# power_schematic.net
KiCad netlist of a schematic drawn in Altium Designer
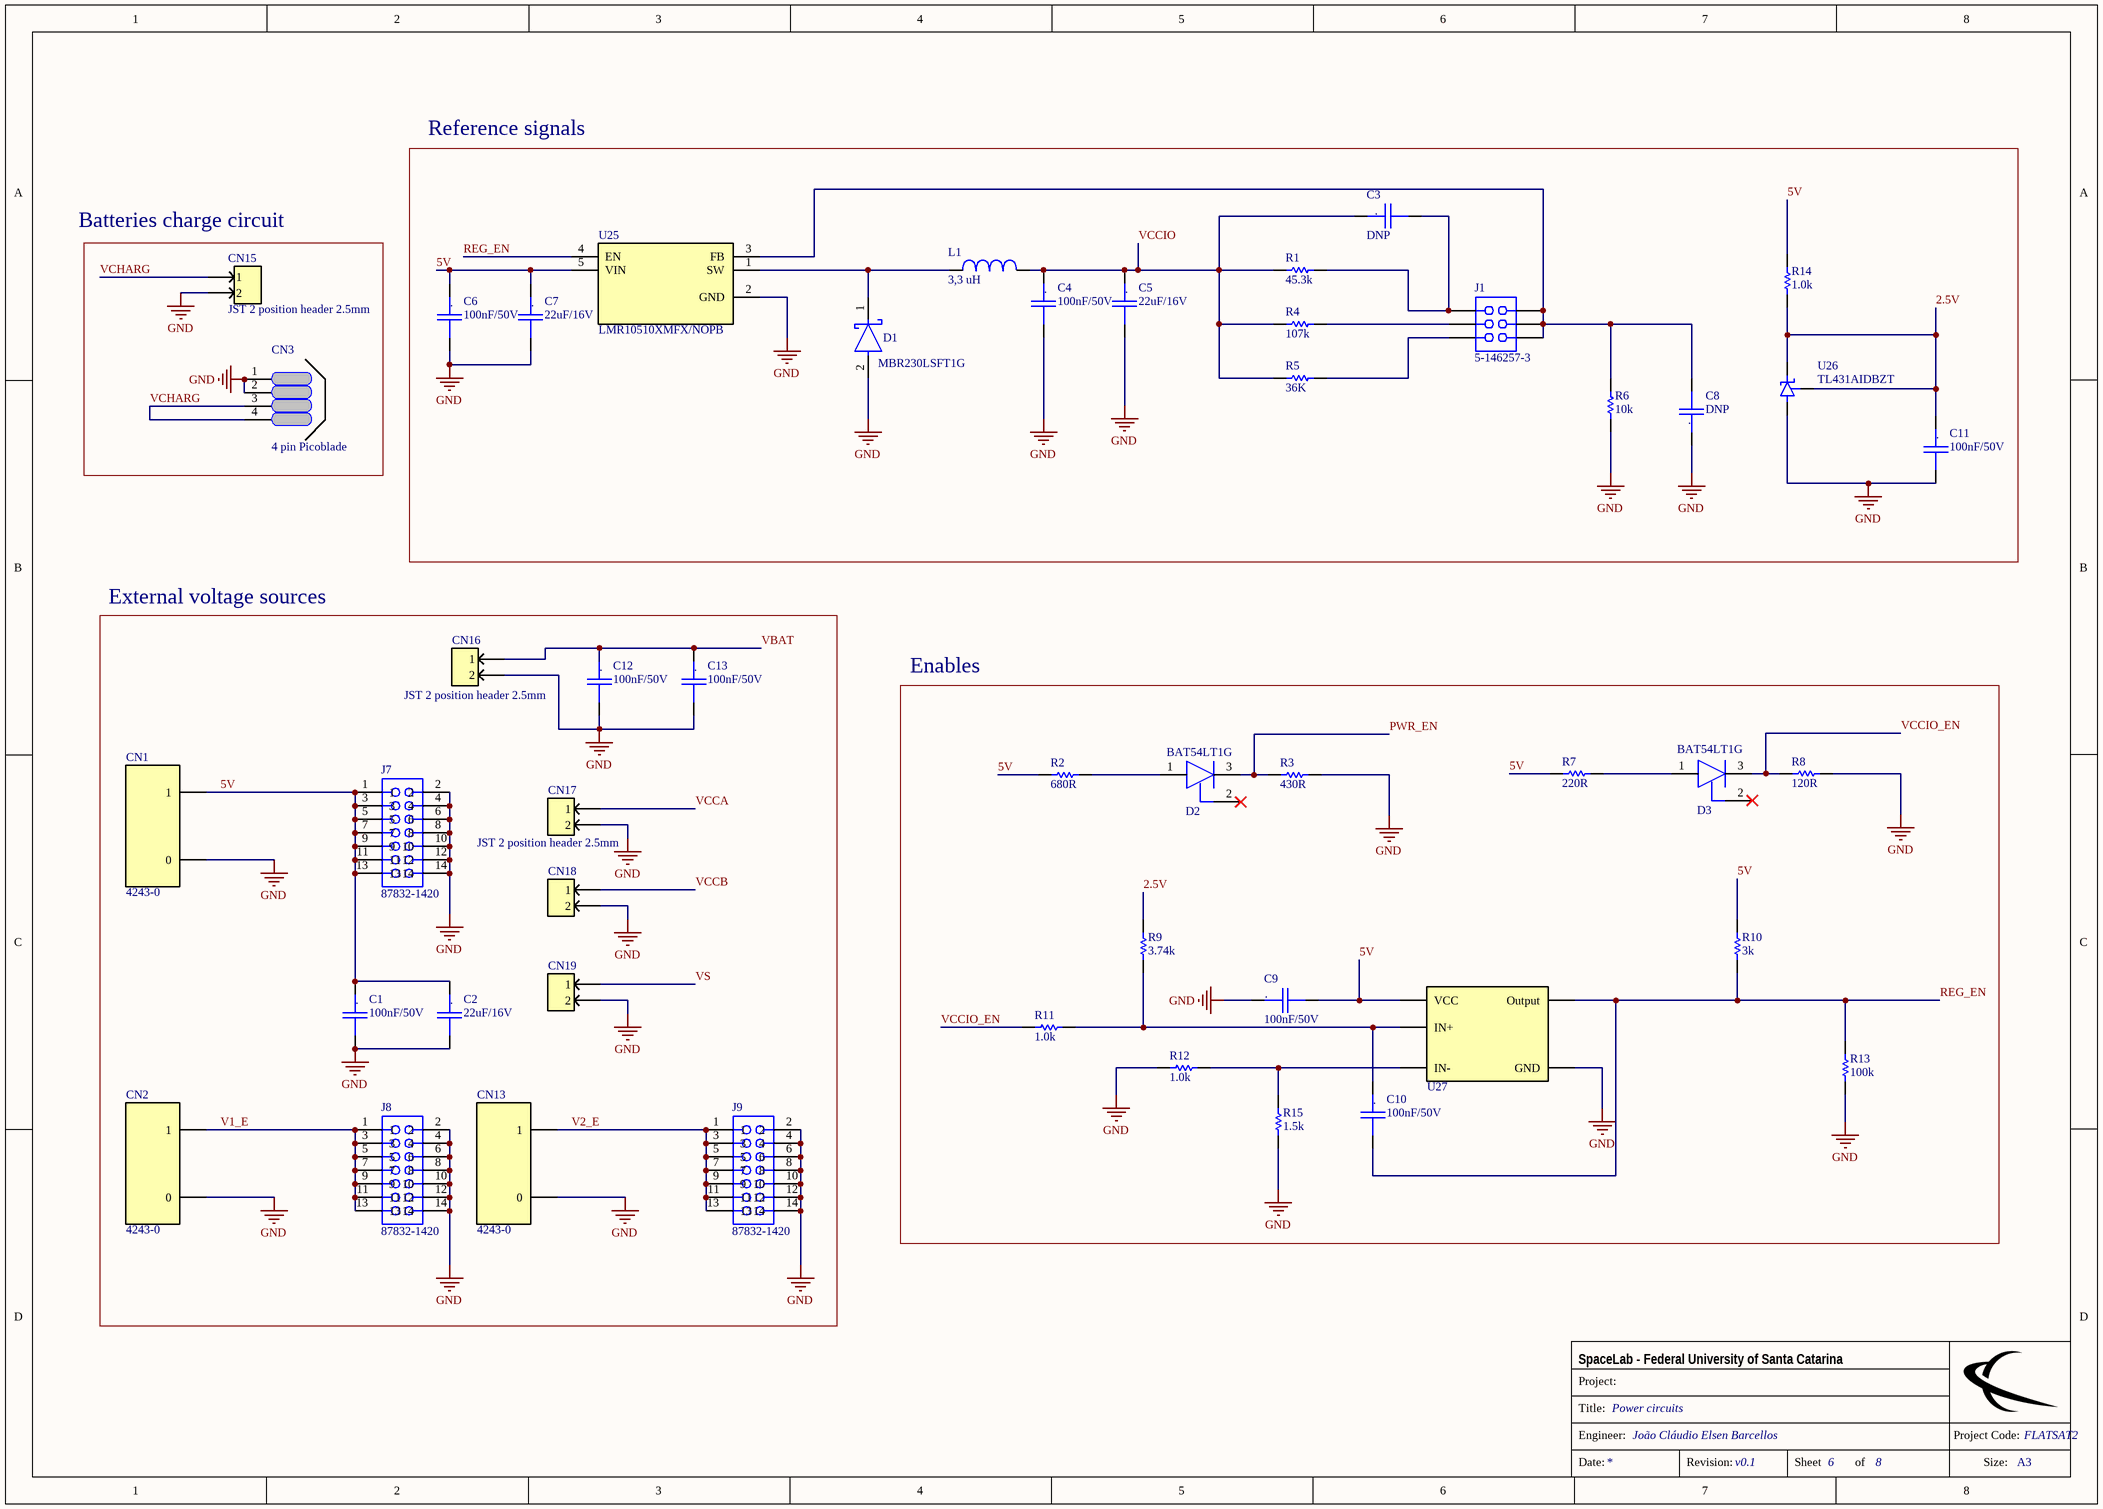
[diagram p0: power_schematic.SchDoc]

(export (version "E")
  (design (tool "Eeschema 10.0.6"))
  (components
    (comp (ref "C1")
      (value "100nF/50V")
      (footprint "CC0603")
      (description "CAP CER 100nF 50V 10% X7R 0603")
      (fields (field (name "MANUFACTURER PART NUMBER") "C0603C104K5RAC3121"))
      (libsource (lib "flatsat_platform_2") (part "Cap_Cer_X7R_100nF_50V_0603"))
    )
    (comp (ref "C2")
      (value "22uF/16V")
      (footprint "CC1210")
      (description "CAP CER 22uF 16V 10% X7R 1210")
      (fields (field (name "MANUFACTURER PART NUMBER") "C3225X7R1C226K250AC"))
      (libsource (lib "flatsat_platform_2") (part "Cap_Cer_X7R_22uF_16V_1210"))
    )
    (comp (ref "C3")
      (value "DNP")
      (footprint "CC0805")
      (description "CAP DNP 0805")
      (libsource (lib "flatsat_platform_2") (part "Cap_DNP_0805"))
    )
    (comp (ref "C4")
      (value "100nF/50V")
      (footprint "CC0603")
      (description "CAP CER 100nF 50V 10% X7R 0603")
      (fields (field (name "MANUFACTURER PART NUMBER") "C0603C104K5RAC3121"))
      (libsource (lib "flatsat_platform_2") (part "Cap_Cer_X7R_100nF_50V_0603"))
    )
    (comp (ref "C5")
      (value "22uF/16V")
      (footprint "CC1210")
      (description "CAP CER 22uF 16V 10% X7R 1210")
      (fields (field (name "MANUFACTURER PART NUMBER") "C3225X7R1C226K250AC"))
      (libsource (lib "flatsat_platform_2") (part "Cap_Cer_X7R_22uF_16V_1210"))
    )
    (comp (ref "C6")
      (value "100nF/50V")
      (footprint "CC0603")
      (description "CAP CER 100nF 50V 10% X7R 0603")
      (fields (field (name "MANUFACTURER PART NUMBER") "C0603C104K5RAC3121"))
      (libsource (lib "flatsat_platform_2") (part "Cap_Cer_X7R_100nF_50V_0603"))
    )
    (comp (ref "C7")
      (value "22uF/16V")
      (footprint "CC1210")
      (description "CAP CER 22uF 16V 10% X7R 1210")
      (fields (field (name "MANUFACTURER PART NUMBER") "C3225X7R1C226K250AC"))
      (libsource (lib "flatsat_platform_2") (part "Cap_Cer_X7R_22uF_16V_1210"))
    )
    (comp (ref "C8")
      (value "DNP")
      (footprint "CC0805")
      (description "CAP DNP 0805")
      (libsource (lib "flatsat_platform_2") (part "Cap_DNP_0805"))
    )
    (comp (ref "C9")
      (value "100nF/50V")
      (footprint "CC0603")
      (description "CAP CER 100nF 50V 10% X7R 0603")
      (fields (field (name "MANUFACTURER PART NUMBER") "C0603C104K5RAC3121"))
      (libsource (lib "flatsat_platform_2") (part "Cap_Cer_X7R_100nF_50V_0603"))
    )
    (comp (ref "C10")
      (value "100nF/50V")
      (footprint "CC0603")
      (description "CAP CER 100nF 50V 10% X7R 0603")
      (fields (field (name "MANUFACTURER PART NUMBER") "C0603C104K5RAC3121"))
      (libsource (lib "flatsat_platform_2") (part "Cap_Cer_X7R_100nF_50V_0603"))
    )
    (comp (ref "C11")
      (value "100nF/50V")
      (footprint "CC0603")
      (description "CAP CER 100nF 50V 10% X7R 0603")
      (fields (field (name "MANUFACTURER PART NUMBER") "C0603C104K5RAC3121"))
      (libsource (lib "flatsat_platform_2") (part "Cap_Cer_X7R_100nF_50V_0603"))
    )
    (comp (ref "C12")
      (value "100nF/50V")
      (footprint "CC0603")
      (description "CAP CER 100nF 50V 10% X7R 0603")
      (fields (field (name "MANUFACTURER PART NUMBER") "C0603C104K5RAC3121"))
      (libsource (lib "flatsat_platform_2") (part "Cap_Cer_X7R_100nF_50V_0603"))
    )
    (comp (ref "C13")
      (value "100nF/50V")
      (footprint "CC0603")
      (description "CAP CER 100nF 50V 10% X7R 0603")
      (fields (field (name "MANUFACTURER PART NUMBER") "C0603C104K5RAC3121"))
      (libsource (lib "flatsat_platform_2") (part "Cap_Cer_X7R_100nF_50V_0603"))
    )
    (comp (ref "CN1")
      (value "4243-0")
      (footprint "4243-0")
      (description "POMONA, 4243-0, Binding Post, 4243 Series, 15 A, 60 VDC, Tin Plated Contacts, Brass, Black")
      (fields (field (name "MANUFACTURER") "Pomona Electronics"))
      (libsource (lib "flatsat_platform_2") (part "4243-0"))
    )
    (comp (ref "CN2")
      (value "4243-0")
      (footprint "4243-0")
      (description "POMONA, 4243-0, Binding Post, 4243 Series, 15 A, 60 VDC, Tin Plated Contacts, Brass, Black")
      (fields (field (name "MANUFACTURER") "Pomona Electronics"))
      (libsource (lib "flatsat_platform_2") (part "4243-0"))
    )
    (comp (ref "CN3")
      (value "4 pin Picoblade")
      (footprint "PICO BLADE 0533980471")
      (description "1.25mm Pitch PicoBlade™ Header, Surface Mount, Vertical, 4 Circuits")
      (fields (field (name "MANUFACTURER") "Molex") (field (name "MANUFACTURER PART NUMBER") "53398-0471"))
      (libsource (lib "flatsat_platform_2") (part "0533980471"))
    )
    (comp (ref "CN13")
      (value "4243-0")
      (footprint "4243-0")
      (description "POMONA, 4243-0, Binding Post, 4243 Series, 15 A, 60 VDC, Tin Plated Contacts, Brass, Black")
      (fields (field (name "MANUFACTURER") "Pomona Electronics"))
      (libsource (lib "flatsat_platform_2") (part "4243-0"))
    )
    (comp (ref "CN15")
      (value "JST 2 position header 2.5mm")
      (footprint "B2B-XH-A-M(LF)(SN)")
      (description "CONN HEADER TOP 2POS 2.5MM GRN")
      (fields
        (field (name "MANUFACTURER") "JST")
        (field (name "MANUFACTURER PART NUMBER") "B2B-XH-A-M(LF)(SN)")
      )
      (libsource (lib "") (part "B2B-XH-A-M(LF)(SN)_1"))
    )
    (comp (ref "CN16")
      (value "JST 2 position header 2.5mm")
      (footprint "B2B-XH-A-M(LF)(SN)")
      (description "CONN HEADER TOP 2POS 2.5MM GRN")
      (fields
        (field (name "MANUFACTURER") "JST")
        (field (name "MANUFACTURER PART NUMBER") "B2B-XH-A-M(LF)(SN)")
      )
      (libsource (lib "flatsat_platform_2") (part "B2B-XH-A-M(LF)(SN)"))
    )
    (comp (ref "CN17")
      (value "JST 2 position header 2.5mm")
      (footprint "B2B-XH-A-M(LF)(SN)")
      (description "CONN HEADER TOP 2POS 2.5MM GRN")
      (fields
        (field (name "MANUFACTURER") "JST")
        (field (name "MANUFACTURER PART NUMBER") "B2B-XH-A-M(LF)(SN)")
      )
      (libsource (lib "flatsat_platform_2") (part "B2B-XH-A-M(LF)(SN)"))
    )
    (comp (ref "CN18")
      (value "JST 2 position header 2.5mm")
      (footprint "B2B-XH-A-M(LF)(SN)")
      (description "CONN HEADER TOP 2POS 2.5MM GRN")
      (fields
        (field (name "MANUFACTURER") "JST")
        (field (name "MANUFACTURER PART NUMBER") "B2B-XH-A-M(LF)(SN)")
      )
      (libsource (lib "flatsat_platform_2") (part "B2B-XH-A-M(LF)(SN)"))
    )
    (comp (ref "CN19")
      (value "JST 2 position header 2.5mm")
      (footprint "B2B-XH-A-M(LF)(SN)")
      (description "CONN HEADER TOP 2POS 2.5MM GRN")
      (fields
        (field (name "MANUFACTURER") "JST")
        (field (name "MANUFACTURER PART NUMBER") "B2B-XH-A-M(LF)(SN)")
      )
      (libsource (lib "flatsat_platform_2") (part "B2B-XH-A-M(LF)(SN)"))
    )
    (comp (ref "D1")
      (value "MBR230LSFT1G")
      (footprint "On_Semiconductor_498_MFG")
      (libsource (lib "flatsat_platform_2") (part "MBR230LSFT1G"))
    )
    (comp (ref "D2")
      (value "BAT54LT1G")
      (footprint "SOT95P237X112-3N")
      (libsource (lib "flatsat_platform_2") (part "BAT54LT1G"))
    )
    (comp (ref "D3")
      (value "BAT54LT1G")
      (footprint "SOT95P237X112-3N")
      (libsource (lib "flatsat_platform_2") (part "BAT54LT1G"))
    )
    (comp (ref "J1")
      (value "5-146257-3")
      (footprint "TE_5-146257-3")
      (description "Header; Breakaway; 0.100 x 0.100 in.; PC Board; Dual; 6; 0.025 in.; 0.12 in.")
      (fields (field (name "MF") "TE Connectivity"))
      (libsource (lib "flatsat_platform_2") (part "5-146257-3"))
    )
    (comp (ref "J7")
      (value "87832-1420")
      (footprint "SAMTEC_TSW-107-05-F-D")
      (description "Connector Header Surface Mount 14 position 0.079 _2.00mm_")
      (fields (field (name "MF") "Molex") (field (name "MANUFACTURER PART NUMBER") "TSW-107-05-F-D"))
      (libsource (lib "flatsat_platform_2") (part "87832-1420"))
    )
    (comp (ref "J8")
      (value "87832-1420")
      (footprint "SAMTEC_TSW-107-05-F-D")
      (description "Connector Header Surface Mount 14 position 0.079 _2.00mm_")
      (fields (field (name "MF") "Molex") (field (name "MANUFACTURER PART NUMBER") "TSW-107-05-F-D"))
      (libsource (lib "flatsat_platform_2") (part "87832-1420"))
    )
    (comp (ref "J9")
      (value "87832-1420")
      (footprint "SAMTEC_TSW-107-05-F-D")
      (description "Connector Header Surface Mount 14 position 0.079 _2.00mm_")
      (fields (field (name "MF") "Molex") (field (name "MANUFACTURER PART NUMBER") "TSW-107-05-F-D"))
      (libsource (lib "flatsat_platform_2") (part "87832-1420"))
    )
    (comp (ref "L1")
      (value "3,3 uH")
      (footprint "SRR6038")
      (description "3.3ÂµH Shielded Wirewound Inductor 3.5A 20mOhm Max Nonstandard")
      (fields (field (name "MF") "Bourns") (field (name "MANUFACTURER PART NUMBER") "SRR6038-3R3Y"))
      (libsource (lib "flatsat_platform_2") (part "3,3 uH"))
    )
    (comp (ref "R1")
      (value "45.3k")
      (footprint "0805")
      (description "RES 45.3K OHM 1/8W 1% 0805")
      (fields (field (name "MANUFACTURER PART NUMBER") "RC0805FR-0745K3L"))
      (libsource (lib "flatsat_platform_2") (part "R45.3k_1%_1/10W_0805"))
    )
    (comp (ref "R2")
      (value "680R")
      (footprint "0805")
      (description "RES 680R OHM 1/8W 1% 0805")
      (fields (field (name "MANUFACTURER PART NUMBER") "CRGCQ0805F680R"))
      (libsource (lib "flatsat_platform_2") (part "R680R_1%_1/8W_0805"))
    )
    (comp (ref "R3")
      (value "430R")
      (footprint "0805")
      (description "RES 430R OHM 1/8W 0.1% 0805")
      (fields (field (name "MANUFACTURER PART NUMBER") "RT0805BRD07430RL"))
      (libsource (lib "flatsat_platform_2") (part "R430R_1%_1/4W_0805"))
    )
    (comp (ref "R4")
      (value "107k")
      (footprint "0805")
      (description "RES 107K OHM 1/8W 1% 0805")
      (fields (field (name "MANUFACTURER PART NUMBER") "RC0805FR-07107KL"))
      (libsource (lib "flatsat_platform_2") (part "R107k_1%_1/8W_0805"))
    )
    (comp (ref "R5")
      (value "36K")
      (footprint "0805")
      (description "RES 36K OHM 1/8W 0.1% 0805")
      (fields (field (name "MANUFACTURER PART NUMBER") "RG2012N-363-B-T5"))
      (libsource (lib "flatsat_platform_2") (part "R36K_1%_1/10W_0805"))
    )
    (comp (ref "R6")
      (value "10k")
      (footprint "0805")
      (description "RES 10K OHM 1/8W 1%  0805")
      (fields (field (name "MANUFACTURER PART NUMBER") "CRCW080510K0FKEA"))
      (libsource (lib "flatsat_platform_2") (part "R10k_1%_1/8W_0805"))
    )
    (comp (ref "R7")
      (value "220R")
      (footprint "0805")
      (description "RES 220R OHM 1/8W 1% 0805")
      (fields (field (name "MANUFACTURER PART NUMBER") "CRCW0805220RFKEA"))
      (libsource (lib "flatsat_platform_2") (part "R220R_1%_1/8W_0805"))
    )
    (comp (ref "R8")
      (value "120R")
      (footprint "0805")
      (description "RES 120R OHM 1/8W 1% 0805")
      (fields (field (name "MANUFACTURER PART NUMBER") "CRGCQ0805F120R"))
      (libsource (lib "flatsat_platform_2") (part "R120R_1%_1/4W_0805"))
    )
    (comp (ref "R9")
      (value "3.74k")
      (footprint "0805")
      (description "RES 3.74K OHM 1/8W 0.5% 0805")
      (fields (field (name "MANUFACTURER PART NUMBER") "RT0805DRE073K74L"))
      (libsource (lib "flatsat_platform_2") (part "R3.74k_1%_1/8W_0805"))
    )
    (comp (ref "R10")
      (value "3k")
      (footprint "0805")
      (description "RES 3.0K OHM 1/10W 0.1% 0805")
      (fields (field (name "MANUFACTURER PART NUMBER") "ERA-6YEB302V"))
      (libsource (lib "flatsat_platform_2") (part "R3.0k_1%_1/8W_0805"))
    )
    (comp (ref "R11")
      (value "1.0k")
      (footprint "0805")
      (description "RES 1.0K OHM 1/8W 1% 0805")
      (fields (field (name "MANUFACTURER PART NUMBER") "RC0805FR-071KL"))
      (libsource (lib "flatsat_platform_2") (part "R1.0k_1%_1/8W_0805"))
    )
    (comp (ref "R12")
      (value "1.0k")
      (footprint "0805")
      (description "RES 1.0K OHM 1/8W 1% 0805")
      (fields (field (name "MANUFACTURER PART NUMBER") "RC0805FR-071KL"))
      (libsource (lib "flatsat_platform_2") (part "R1.0k_1%_1/8W_0805"))
    )
    (comp (ref "R13")
      (value "100k")
      (footprint "0805")
      (description "RES 100K OHM 1/8W 1% 0805")
      (fields (field (name "MANUFACTURER PART NUMBER") "AC0805FR-13100KL"))
      (libsource (lib "flatsat_platform_2") (part "R100k_1%_1/8W_0805"))
    )
    (comp (ref "R14")
      (value "1.0k")
      (footprint "0805")
      (description "RES 1.0K OHM 1/8W 1% 0805")
      (fields (field (name "MANUFACTURER PART NUMBER") "RC0805FR-071KL"))
      (libsource (lib "flatsat_platform_2") (part "R1.0k_1%_1/8W_0805"))
    )
    (comp (ref "R15")
      (value "1.5k")
      (footprint "0805")
      (description "RES 1.5K OHM 1/10W 0.1% 0805")
      (fields (field (name "MANUFACTURER PART NUMBER") "RN73C2A1K5BTDF"))
      (libsource (lib "flatsat_platform_2") (part "R1.5K_1%_1/10W_0805"))
    )
    (comp (ref "U25")
      (value "LMR10510XMFX/NOPB")
      (footprint "SOT95P280X145-5N")
      (libsource (lib "flatsat_platform_2") (part "LMR10510XMFX/NOPB"))
    )
    (comp (ref "U26")
      (value "TL431AIDBZT")
      (footprint "SOT95P237X112-3N")
      (description "Shunt Voltage Reference IC 36V Â±1% SOT-23-3")
      (fields (field (name "MF") "Texas Instruments"))
      (libsource (lib "flatsat_platform_2") (part "TL431AIDBZT"))
    )
    (comp (ref "U27")
      (value "AP331AWG-7")
      (footprint "SOT95P280X145-5N")
      (libsource (lib "flatsat_platform_2") (part "AP331AWG-7"))
    )
  )
  (nets
    (net (code "1") (name "/2.5V") (class "Default")
      (node (ref "C11") (pin "1") (pinfunction "1_1") (pintype "passive"))
      (node (ref "R14") (pin "1") (pinfunction "1_1") (pintype "passive"))
      (node (ref "R9") (pin "2") (pinfunction "2_2") (pintype "passive"))
      (node (ref "U26") (pin "1") (pinfunction "CATHODE_1") (pintype "passive"))
      (node (ref "U26") (pin "2") (pinfunction "REF_2") (pintype "passive"))
    )
    (net (code "2") (name "/5V") (class "Default")
      (node (ref "C1") (pin "1") (pinfunction "1_1") (pintype "passive"))
      (node (ref "C2") (pin "1") (pinfunction "1_1") (pintype "passive"))
      (node (ref "C6") (pin "1") (pinfunction "1_1") (pintype "passive"))
      (node (ref "C7") (pin "1") (pinfunction "1_1") (pintype "passive"))
      (node (ref "C9") (pin "2") (pinfunction "2_2") (pintype "passive"))
      (node (ref "CN1") (pin "1") (pinfunction "1_1") (pintype "passive"))
      (node (ref "J7") (pin "1") (pinfunction "1_1") (pintype "passive"))
      (node (ref "J7") (pin "11") (pinfunction "11_11") (pintype "passive"))
      (node (ref "J7") (pin "13") (pinfunction "13_13") (pintype "passive"))
      (node (ref "J7") (pin "3") (pinfunction "3_3") (pintype "passive"))
      (node (ref "J7") (pin "5") (pinfunction "5_5") (pintype "passive"))
      (node (ref "J7") (pin "7") (pinfunction "7_7") (pintype "passive"))
      (node (ref "J7") (pin "9") (pinfunction "9_9") (pintype "passive"))
      (node (ref "R10") (pin "2") (pinfunction "2_2") (pintype "passive"))
      (node (ref "R14") (pin "2") (pinfunction "2_2") (pintype "passive"))
      (node (ref "R2") (pin "2") (pinfunction "2_2") (pintype "passive"))
      (node (ref "R7") (pin "2") (pinfunction "2_2") (pintype "passive"))
      (node (ref "U25") (pin "5") (pinfunction "VIN_5") (pintype "power_in"))
      (node (ref "U27") (pin "5") (pinfunction "VCC_5") (pintype "power_in"))
    )
    (net (code "3") (name "/PWR_EN") (class "Default")
      (node (ref "D2") (pin "3") (pinfunction "C_3") (pintype "passive"))
      (node (ref "R3") (pin "2") (pinfunction "2_2") (pintype "passive"))
    )
    (net (code "4") (name "/REG_EN") (class "Default")
      (node (ref "C10") (pin "2") (pinfunction "2_2") (pintype "passive"))
      (node (ref "R10") (pin "1") (pinfunction "1_1") (pintype "passive"))
      (node (ref "R13") (pin "2") (pinfunction "2_2") (pintype "passive"))
      (node (ref "U25") (pin "4") (pinfunction "EN_4") (pintype "power_in"))
      (node (ref "U27") (pin "4") (pinfunction "Output_4") (pintype "power_in"))
    )
    (net (code "5") (name "/V1_E") (class "Default")
      (node (ref "CN2") (pin "1") (pinfunction "1_1") (pintype "passive"))
      (node (ref "J8") (pin "1") (pinfunction "1_1") (pintype "passive"))
      (node (ref "J8") (pin "11") (pinfunction "11_11") (pintype "passive"))
      (node (ref "J8") (pin "13") (pinfunction "13_13") (pintype "passive"))
      (node (ref "J8") (pin "3") (pinfunction "3_3") (pintype "passive"))
      (node (ref "J8") (pin "5") (pinfunction "5_5") (pintype "passive"))
      (node (ref "J8") (pin "7") (pinfunction "7_7") (pintype "passive"))
      (node (ref "J8") (pin "9") (pinfunction "9_9") (pintype "passive"))
    )
    (net (code "6") (name "/V2_E") (class "Default")
      (node (ref "CN13") (pin "1") (pinfunction "1_1") (pintype "passive"))
      (node (ref "J9") (pin "1") (pinfunction "1_1") (pintype "passive"))
      (node (ref "J9") (pin "11") (pinfunction "11_11") (pintype "passive"))
      (node (ref "J9") (pin "13") (pinfunction "13_13") (pintype "passive"))
      (node (ref "J9") (pin "3") (pinfunction "3_3") (pintype "passive"))
      (node (ref "J9") (pin "5") (pinfunction "5_5") (pintype "passive"))
      (node (ref "J9") (pin "7") (pinfunction "7_7") (pintype "passive"))
      (node (ref "J9") (pin "9") (pinfunction "9_9") (pintype "passive"))
    )
    (net (code "7") (name "/VBAT") (class "Default")
      (node (ref "C12") (pin "1") (pinfunction "1_1") (pintype "passive"))
      (node (ref "C13") (pin "1") (pinfunction "1_1") (pintype "passive"))
      (node (ref "CN16") (pin "1") (pinfunction "1_1") (pintype "passive"))
    )
    (net (code "8") (name "/VCCA") (class "Default")
      (node (ref "CN17") (pin "1") (pinfunction "1_1") (pintype "passive"))
    )
    (net (code "9") (name "/VCCB") (class "Default")
      (node (ref "CN18") (pin "1") (pinfunction "1_1") (pintype "passive"))
    )
    (net (code "10") (name "/VCCIO") (class "Default")
      (node (ref "C3") (pin "1") (pinfunction "1_1") (pintype "passive"))
      (node (ref "C4") (pin "1") (pinfunction "1_1") (pintype "passive"))
      (node (ref "C5") (pin "1") (pinfunction "1_1") (pintype "passive"))
      (node (ref "L1") (pin "2") (pinfunction "2_2") (pintype "passive"))
      (node (ref "R1") (pin "2") (pinfunction "2_2") (pintype "passive"))
      (node (ref "R4") (pin "2") (pinfunction "2_2") (pintype "passive"))
      (node (ref "R5") (pin "2") (pinfunction "2_2") (pintype "passive"))
    )
    (net (code "11") (name "/VCCIO_EN") (class "Default")
      (node (ref "D3") (pin "3") (pinfunction "C_3") (pintype "passive"))
      (node (ref "R11") (pin "2") (pinfunction "2_2") (pintype "passive"))
      (node (ref "R8") (pin "2") (pinfunction "2_2") (pintype "passive"))
    )
    (net (code "12") (name "/VCHARG") (class "Default")
      (node (ref "CN15") (pin "1") (pinfunction "1_1") (pintype "passive"))
      (node (ref "CN3") (pin "3") (pinfunction "3_3") (pintype "passive"))
      (node (ref "CN3") (pin "4") (pinfunction "4_4") (pintype "passive"))
    )
    (net (code "13") (name "/VS") (class "Default")
      (node (ref "CN19") (pin "1") (pinfunction "1_1") (pintype "passive"))
    )
    (net (code "14") (name "GND") (class "Default")
      (node (ref "C1") (pin "2") (pinfunction "2_2") (pintype "passive"))
      (node (ref "C11") (pin "2") (pinfunction "2_2") (pintype "passive"))
      (node (ref "C12") (pin "2") (pinfunction "2_2") (pintype "passive"))
      (node (ref "C13") (pin "2") (pinfunction "2_2") (pintype "passive"))
      (node (ref "C2") (pin "2") (pinfunction "2_2") (pintype "passive"))
      (node (ref "C4") (pin "2") (pinfunction "2_2") (pintype "passive"))
      (node (ref "C5") (pin "2") (pinfunction "2_2") (pintype "passive"))
      (node (ref "C6") (pin "2") (pinfunction "2_2") (pintype "passive"))
      (node (ref "C7") (pin "2") (pinfunction "2_2") (pintype "passive"))
      (node (ref "C8") (pin "1") (pinfunction "1_1") (pintype "passive"))
      (node (ref "C9") (pin "1") (pinfunction "1_1") (pintype "passive"))
      (node (ref "CN1") (pin "0") (pinfunction "0_0") (pintype "passive"))
      (node (ref "CN13") (pin "0") (pinfunction "0_0") (pintype "passive"))
      (node (ref "CN15") (pin "2") (pinfunction "2_2") (pintype "passive"))
      (node (ref "CN16") (pin "2") (pinfunction "2_2") (pintype "passive"))
      (node (ref "CN17") (pin "2") (pinfunction "2_2") (pintype "passive"))
      (node (ref "CN18") (pin "2") (pinfunction "2_2") (pintype "passive"))
      (node (ref "CN19") (pin "2") (pinfunction "2_2") (pintype "passive"))
      (node (ref "CN2") (pin "0") (pinfunction "0_0") (pintype "passive"))
      (node (ref "CN3") (pin "1") (pinfunction "1_1") (pintype "passive"))
      (node (ref "CN3") (pin "2") (pinfunction "2_2") (pintype "passive"))
      (node (ref "D1") (pin "2") (pinfunction "A_2") (pintype "passive"))
      (node (ref "J7") (pin "10") (pinfunction "10_10") (pintype "passive"))
      (node (ref "J7") (pin "12") (pinfunction "12_12") (pintype "passive"))
      (node (ref "J7") (pin "14") (pinfunction "14_14") (pintype "passive"))
      (node (ref "J7") (pin "2") (pinfunction "2_2") (pintype "passive"))
      (node (ref "J7") (pin "4") (pinfunction "4_4") (pintype "passive"))
      (node (ref "J7") (pin "6") (pinfunction "6_6") (pintype "passive"))
      (node (ref "J7") (pin "8") (pinfunction "8_8") (pintype "passive"))
      (node (ref "J8") (pin "10") (pinfunction "10_10") (pintype "passive"))
      (node (ref "J8") (pin "12") (pinfunction "12_12") (pintype "passive"))
      (node (ref "J8") (pin "14") (pinfunction "14_14") (pintype "passive"))
      (node (ref "J8") (pin "2") (pinfunction "2_2") (pintype "passive"))
      (node (ref "J8") (pin "4") (pinfunction "4_4") (pintype "passive"))
      (node (ref "J8") (pin "6") (pinfunction "6_6") (pintype "passive"))
      (node (ref "J8") (pin "8") (pinfunction "8_8") (pintype "passive"))
      (node (ref "J9") (pin "10") (pinfunction "10_10") (pintype "passive"))
      (node (ref "J9") (pin "12") (pinfunction "12_12") (pintype "passive"))
      (node (ref "J9") (pin "14") (pinfunction "14_14") (pintype "passive"))
      (node (ref "J9") (pin "2") (pinfunction "2_2") (pintype "passive"))
      (node (ref "J9") (pin "4") (pinfunction "4_4") (pintype "passive"))
      (node (ref "J9") (pin "6") (pinfunction "6_6") (pintype "passive"))
      (node (ref "J9") (pin "8") (pinfunction "8_8") (pintype "passive"))
      (node (ref "R12") (pin "2") (pinfunction "2_2") (pintype "passive"))
      (node (ref "R13") (pin "1") (pinfunction "1_1") (pintype "passive"))
      (node (ref "R15") (pin "1") (pinfunction "1_1") (pintype "passive"))
      (node (ref "R3") (pin "1") (pinfunction "1_1") (pintype "passive"))
      (node (ref "R6") (pin "1") (pinfunction "1_1") (pintype "passive"))
      (node (ref "R8") (pin "1") (pinfunction "1_1") (pintype "passive"))
      (node (ref "U25") (pin "2") (pinfunction "GND_2") (pintype "power_in"))
      (node (ref "U26") (pin "3") (pinfunction "ANODE_3") (pintype "passive"))
      (node (ref "U27") (pin "2") (pinfunction "GND_2") (pintype "power_in"))
    )
    (net (code "15") (name "Net-(C3-Pad2)") (class "Default")
      (node (ref "C3") (pin "2") (pinfunction "2_2") (pintype "passive"))
      (node (ref "J1") (pin "1") (pinfunction "1_1") (pintype "passive"))
      (node (ref "R1") (pin "1") (pinfunction "1_1") (pintype "passive"))
    )
    (net (code "16") (name "Net-(D1-C)") (class "Default")
      (node (ref "D1") (pin "1") (pinfunction "C_1") (pintype "passive"))
      (node (ref "L1") (pin "1") (pinfunction "1_1") (pintype "passive"))
      (node (ref "U25") (pin "1") (pinfunction "SW_1") (pintype "power_in"))
    )
    (net (code "17") (name "Net-(D2-A)") (class "Default")
      (node (ref "D2") (pin "1") (pinfunction "A_1") (pintype "passive"))
      (node (ref "R2") (pin "1") (pinfunction "1_1") (pintype "passive"))
    )
    (net (code "18") (name "Net-(D3-A)") (class "Default")
      (node (ref "D3") (pin "1") (pinfunction "A_1") (pintype "passive"))
      (node (ref "R7") (pin "1") (pinfunction "1_1") (pintype "passive"))
    )
    (net (code "19") (name "Net-(J1-Pad3)") (class "Default")
      (node (ref "J1") (pin "3") (pinfunction "3_3") (pintype "passive"))
      (node (ref "R4") (pin "1") (pinfunction "1_1") (pintype "passive"))
    )
    (net (code "20") (name "Net-(J1-Pad5)") (class "Default")
      (node (ref "J1") (pin "5") (pinfunction "5_5") (pintype "passive"))
      (node (ref "R5") (pin "1") (pinfunction "1_1") (pintype "passive"))
    )
    (net (code "21") (name "Net-(U25-FB)") (class "Default")
      (node (ref "C8") (pin "2") (pinfunction "2_2") (pintype "passive"))
      (node (ref "J1") (pin "2") (pinfunction "2_2") (pintype "passive"))
      (node (ref "J1") (pin "4") (pinfunction "4_4") (pintype "passive"))
      (node (ref "J1") (pin "6") (pinfunction "6_6") (pintype "passive"))
      (node (ref "R6") (pin "2") (pinfunction "2_2") (pintype "passive"))
      (node (ref "U25") (pin "3") (pinfunction "FB_3") (pintype "power_in"))
    )
    (net (code "22") (name "Net-(U27-IN+)") (class "Default")
      (node (ref "C10") (pin "1") (pinfunction "1_1") (pintype "passive"))
      (node (ref "R11") (pin "1") (pinfunction "1_1") (pintype "passive"))
      (node (ref "R9") (pin "1") (pinfunction "1_1") (pintype "passive"))
      (node (ref "U27") (pin "3") (pinfunction "IN+_3") (pintype "tri_state"))
    )
    (net (code "23") (name "Net-(U27-IN-)") (class "Default")
      (node (ref "R12") (pin "1") (pinfunction "1_1") (pintype "passive"))
      (node (ref "R15") (pin "2") (pinfunction "2_2") (pintype "passive"))
      (node (ref "U27") (pin "1") (pinfunction "IN-_1") (pintype "tri_state"))
    )
    (net (code "24") (name "unconnected-(D2-NC-Pad2)") (class "Default")
      (node (ref "D2") (pin "2") (pinfunction "NC_2") (pintype "passive+no_connect"))
    )
    (net (code "25") (name "unconnected-(D3-NC-Pad2)") (class "Default")
      (node (ref "D3") (pin "2") (pinfunction "NC_2") (pintype "passive+no_connect"))
    )
  )
)
